# ProPrj_CGM_BH66F2455_HT32F67595_V1_0.net
KiCad netlist of a schematic drawn in EasyEDA Pro
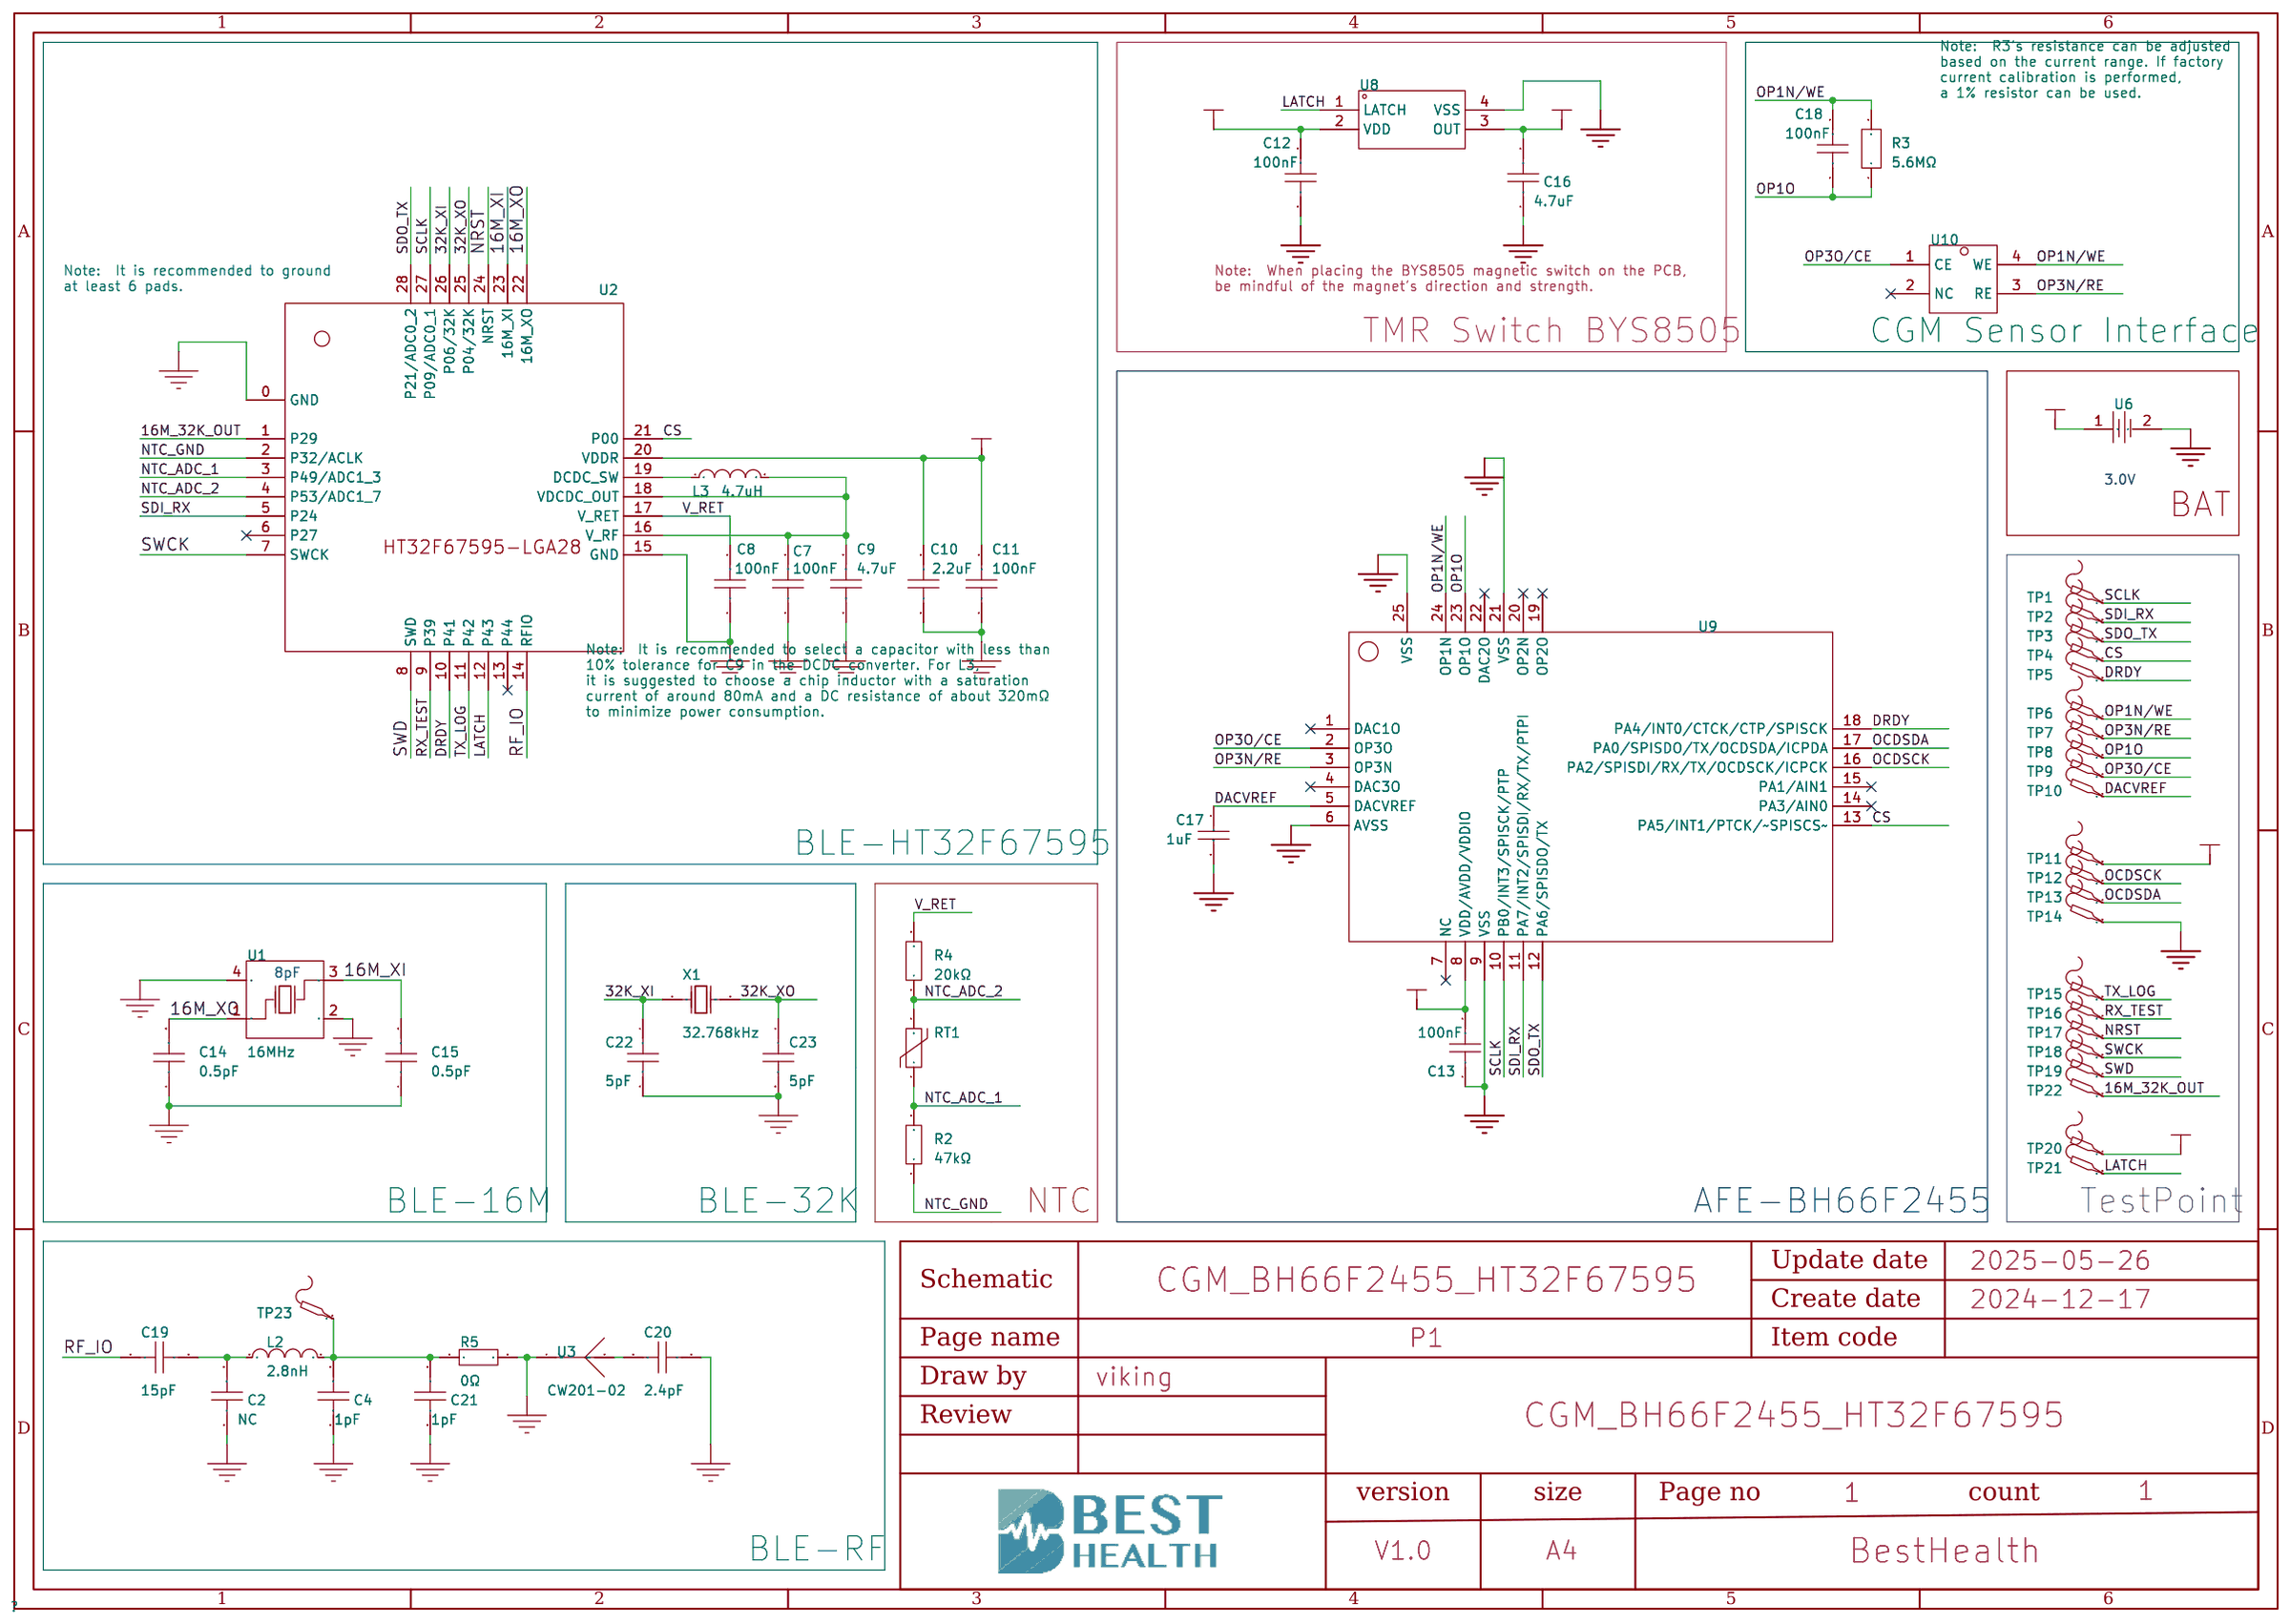
[diagram p0: schematic sheet]

(export (version "E")
  (design (tool "Eeschema 10.0.6"))
  (components
    (comp (ref "C2")
      (value "1.2pF")
      (footprint "easyedapro:C0201")
      (description "容值:1.2pF;额定电压:50V;材质(温度系数):C0G;")
      (fields
        (field (name "Manufacturer Part") "GJM0335C1H1R2WB01D")
        (field (name "Manufacturer") "muRata(村田)")
      )
      (libsource (lib "easyedapro") (part "GJM0335C1H1R2WB01D"))
    )
    (comp (ref "C4")
      (value "1pF")
      (footprint "easyedapro:C0201")
      (description "容值:1pF;精度:-;额定电压:50V;材质(温度系数):C0G;")
      (fields
        (field (name "Manufacturer Part") "GRM0335C1H1R0BA01D")
        (field (name "Manufacturer") "muRata(村田)")
      )
      (libsource (lib "easyedapro") (part "GRM0335C1H1R0BA01D"))
    )
    (comp (ref "C7")
      (value "100nF")
      (footprint "easyedapro:C0201")
      (description "容值:100nF;精度:±10%;额定电压:16V;材质(温度系数):X5R;")
      (fields
        (field (name "Manufacturer Part") "CL03A104KO3NNNC")
        (field (name "Manufacturer") "SAMSUNG(三星)")
      )
      (libsource (lib "easyedapro") (part "CL03A104KO3NNNC"))
    )
    (comp (ref "C8")
      (value "100nF")
      (footprint "easyedapro:C0201")
      (description "容值:100nF;精度:±10%;额定电压:16V;材质(温度系数):X5R;")
      (fields
        (field (name "Manufacturer Part") "CL03A104KO3NNNC")
        (field (name "Manufacturer") "SAMSUNG(三星)")
      )
      (libsource (lib "easyedapro") (part "CL03A104KO3NNNC"))
    )
    (comp (ref "C9")
      (value "4.7uF")
      (footprint "easyedapro:C0402")
      (description "容值:4.7uF;精度:±10%;额定电压:10V;材质(温度系数):X5R;")
      (fields
        (field (name "Manufacturer Part") "CC0402KRX5R6BB475")
        (field (name "Manufacturer") "YAGEO(国巨)")
      )
      (libsource (lib "easyedapro") (part "CC0402KRX5R6BB475"))
    )
    (comp (ref "C10")
      (value "2.2uF")
      (footprint "easyedapro:C0201")
      (description "容值:2.2uF;精度:±20%;额定电压:10V;材质(温度系数):X5R;")
      (fields
        (field (name "Manufacturer Part") "GRM033R61A225ME47D")
        (field (name "Manufacturer") "muRata(村田)")
      )
      (libsource (lib "easyedapro") (part "GRM033R61A225ME47D"))
    )
    (comp (ref "C11")
      (value "100nF")
      (footprint "easyedapro:C0201")
      (description "容值:100nF;精度:±10%;额定电压:16V;材质(温度系数):X5R;")
      (fields
        (field (name "Manufacturer Part") "CL03A104KO3NNNC")
        (field (name "Manufacturer") "SAMSUNG(三星)")
      )
      (libsource (lib "easyedapro") (part "CL03A104KO3NNNC"))
    )
    (comp (ref "C12")
      (value "100nF")
      (footprint "easyedapro:C0201")
      (description "容值:100nF;精度:±10%;额定电压:16V;材质(温度系数):X5R;")
      (fields
        (field (name "Manufacturer Part") "CL03A104KO3NNNC")
        (field (name "Manufacturer") "SAMSUNG(三星)")
      )
      (libsource (lib "easyedapro") (part "CL03A104KO3NNNC"))
    )
    (comp (ref "C13")
      (value "100nF")
      (footprint "easyedapro:C0201")
      (description "容值:100nF;精度:±10%;额定电压:16V;材质(温度系数):X5R;")
      (fields
        (field (name "Manufacturer Part") "CL03A104KO3NNNC")
        (field (name "Manufacturer") "SAMSUNG(三星)")
      )
      (libsource (lib "easyedapro") (part "CL03A104KO3NNNC"))
    )
    (comp (ref "C14")
      (value "0.5pF")
      (footprint "easyedapro:C0201")
      (description "容值:0.5pF;额定电压:50V;温度系数:C0G;")
      (fields
        (field (name "Manufacturer Part") "GRM0335C1HR50BA01D")
        (field (name "Manufacturer") "muRata(村田)")
      )
      (libsource (lib "easyedapro") (part "GRM0335C1HR50BA01D"))
    )
    (comp (ref "C15")
      (value "0.5pF")
      (footprint "easyedapro:C0201")
      (description "容值:0.5pF;额定电压:50V;温度系数:C0G;")
      (fields
        (field (name "Manufacturer Part") "GRM0335C1HR50BA01D")
        (field (name "Manufacturer") "muRata(村田)")
      )
      (libsource (lib "easyedapro") (part "GRM0335C1HR50BA01D"))
    )
    (comp (ref "C16")
      (value "4.7uF")
      (footprint "easyedapro:C0201")
      (description "容值:4.7uF;精度:±20%;额定电压:6.3V;材质(温度系数):X5R;")
      (fields
        (field (name "Manufacturer Part") "GRM035R60J475ME15D")
        (field (name "Manufacturer") "muRata(村田)")
      )
      (libsource (lib "easyedapro") (part "GRM035R60J475ME15D"))
    )
    (comp (ref "C17")
      (value "1uF")
      (footprint "easyedapro:C0201")
      (description "容值:1uF;精度:±20%;额定电压:6.3V;材质(温度系数):X5R;")
      (fields
        (field (name "Manufacturer Part") "CL03A105MQ3CSNH")
        (field (name "Manufacturer") "SAMSUNG(三星)")
      )
      (libsource (lib "easyedapro") (part "CL03A105MQ3CSNH"))
    )
    (comp (ref "C18")
      (value "100nF")
      (footprint "easyedapro:C0201")
      (description "容值:100nF;精度:±10%;额定电压:16V;材质(温度系数):X5R;")
      (fields
        (field (name "Manufacturer Part") "CL03A104KO3NNNC")
        (field (name "Manufacturer") "SAMSUNG(三星)")
      )
      (libsource (lib "easyedapro") (part "CL03A104KO3NNNC"))
    )
    (comp (ref "C19")
      (value "15pF")
      (footprint "easyedapro:C0201")
      (description "容值:15pF;精度:±5%;额定电压:50V;温度系数:C0G;")
      (fields
        (field (name "Manufacturer Part") "GRM0335C1H150JA01D")
        (field (name "Manufacturer") "muRata(村田)")
      )
      (libsource (lib "easyedapro") (part "GRM0335C1H150JA01D"))
    )
    (comp (ref "C20")
      (value "2.4pF")
      (footprint "easyedapro:C0201")
      (description "容值:2.4pF;额定电压:25V;温度系数:C0G;")
      (fields
        (field (name "Manufacturer Part") "GRM0335C1E2R4CA01D")
        (field (name "Manufacturer") "muRata(村田)")
      )
      (libsource (lib "easyedapro") (part "GRM0335C1E2R4CA01D"))
    )
    (comp (ref "C21")
      (value "1pF")
      (footprint "easyedapro:C0201")
      (description "容值:1pF;精度:-;额定电压:50V;材质(温度系数):C0G;")
      (fields
        (field (name "Manufacturer Part") "GRM0335C1H1R0BA01D")
        (field (name "Manufacturer") "muRata(村田)")
      )
      (libsource (lib "easyedapro") (part "GRM0335C1H1R0BA01D"))
    )
    (comp (ref "C22")
      (value "5pF")
      (footprint "easyedapro:C0201")
      (description "容值:5pF;额定电压:25V;材质(温度系数):C0G;")
      (fields
        (field (name "Manufacturer Part") "GJM0335C1E5R0BB01D")
        (field (name "Manufacturer") "muRata(村田)")
      )
      (libsource (lib "easyedapro") (part "GJM0335C1E5R0BB01D"))
    )
    (comp (ref "C23")
      (value "5pF")
      (footprint "easyedapro:C0201")
      (description "容值:5pF;额定电压:25V;材质(温度系数):C0G;")
      (fields
        (field (name "Manufacturer Part") "GJM0335C1E5R0BB01D")
        (field (name "Manufacturer") "muRata(村田)")
      )
      (libsource (lib "easyedapro") (part "GJM0335C1E5R0BB01D"))
    )
    (comp (ref "L2")
      (value "2.8nH")
      (footprint "easyedapro:L0201-RD")
      (description "电感值:2.8nH;精度:-;额定电流:450mA;饱和电流(Isat):-;直流电阻(DCR):250mΩ;")
      (fields (field (name "Manufacturer Part") "LQP03TG2N8B02D") (field (name "Manufacturer") "muRata(村田)"))
      (libsource (lib "easyedapro") (part "LQP03TG2N8B02D"))
    )
    (comp (ref "L3")
      (value "4.7uH")
      (footprint "easyedapro:L0603")
      (description "电感值:4.7uH;精度:±20%;额定电流:-;饱和电流(Isat):80mA;直流电阻(DCR):320mΩ;")
      (fields (field (name "Manufacturer Part") "MLZ1608N4R7LT000") (field (name "Manufacturer") "TDK"))
      (libsource (lib "easyedapro") (part "MLZ1608N4R7LT000"))
    )
    (comp (ref "R2")
      (value "47kΩ")
      (footprint "easyedapro:R0201")
      (description "电阻类型:厚膜电阻;阻值:47kΩ;精度:±1%;功率:50mW;温度系数:±200ppm/°C;最大工作电压:25V;工作温度范围:-55°C~+155°C;")
      (fields (field (name "Manufacturer Part") "RC0201FR-0747KL") (field (name "Manufacturer") "YAGEO(国巨)"))
      (libsource (lib "easyedapro") (part "RC0201FR-0747KL"))
    )
    (comp (ref "R3")
      (value "5.6MΩ")
      (footprint "easyedapro:R0402")
      (description "电阻类型:厚膜电阻;阻值:5.6MΩ;精度:±1%;功率:62.5mW;最大工作电压:50V;温度系数:±100ppm/°C;")
      (fields (field (name "Manufacturer Part") "RC0402FR-075M6L") (field (name "Manufacturer") "YAGEO(国巨)"))
      (libsource (lib "easyedapro") (part "RC0402FR-075M6L"))
    )
    (comp (ref "R4")
      (value "20kΩ")
      (footprint "easyedapro:R0201")
      (description "电阻类型:厚膜电阻;阻值:20kΩ;精度:±1%;功率:50mW;最大工作电压:25V;温度系数:±200ppm/°C;")
      (fields (field (name "Manufacturer Part") "RC0201FR-0720KL") (field (name "Manufacturer") "YAGEO(国巨)"))
      (libsource (lib "easyedapro") (part "RC0201FR-0720KL_C295787"))
    )
    (comp (ref "R5")
      (value "0Ω")
      (footprint "easyedapro:R0201")
      (description "电阻类型:厚膜电阻;阻值:0Ω;精度:±1%;功率:50mW;最大工作电压:25V;温度系数:-;")
      (fields (field (name "Manufacturer Part") "RC0201FR-070RL") (field (name "Manufacturer") "YAGEO(国巨)"))
      (libsource (lib "easyedapro") (part "RC0201FR-070RL"))
    )
    (comp (ref "RT1")
      (value "NTCG064BF473FTBX")
      (footprint "easyedapro:R0201")
      (description "阻值(25°C):47kΩ;电阻精度:±1%;B值精度:±1%;B值(25°C/50°C):4050K;功率:100mW;最大稳态电流(25°C):140uA;")
      (fields (field (name "Manufacturer") "TDK"))
      (libsource (lib "easyedapro") (part "NTCG064BF473FTBX"))
    )
    (comp (ref "TP1")
      (value "TP1")
      (footprint "easyedapro:Test-Point-0.5mm")
      (description "Test Point 测试点")
      (libsource (lib "easyedapro") (part "Test-Point"))
    )
    (comp (ref "TP2")
      (value "TP1")
      (footprint "easyedapro:Test-Point-0.5mm")
      (description "Test Point 测试点")
      (libsource (lib "easyedapro") (part "Test-Point"))
    )
    (comp (ref "TP3")
      (value "TP1")
      (footprint "easyedapro:Test-Point-0.5mm")
      (description "Test Point 测试点")
      (libsource (lib "easyedapro") (part "Test-Point"))
    )
    (comp (ref "TP4")
      (value "TP1")
      (footprint "easyedapro:Test-Point-0.5mm")
      (description "Test Point 测试点")
      (libsource (lib "easyedapro") (part "Test-Point"))
    )
    (comp (ref "TP5")
      (value "TP1")
      (footprint "easyedapro:Test-Point-0.5mm")
      (description "Test Point 测试点")
      (libsource (lib "easyedapro") (part "Test-Point"))
    )
    (comp (ref "TP6")
      (value "TP1")
      (footprint "easyedapro:Test-Point-0.5mm")
      (description "Test Point 测试点")
      (libsource (lib "easyedapro") (part "Test-Point"))
    )
    (comp (ref "TP7")
      (value "TP1")
      (footprint "easyedapro:Test-Point-0.5mm")
      (description "Test Point 测试点")
      (libsource (lib "easyedapro") (part "Test-Point"))
    )
    (comp (ref "TP8")
      (value "TP1")
      (footprint "easyedapro:Test-Point-0.5mm")
      (description "Test Point 测试点")
      (libsource (lib "easyedapro") (part "Test-Point"))
    )
    (comp (ref "TP9")
      (value "TP1")
      (footprint "easyedapro:Test-Point-0.5mm")
      (description "Test Point 测试点")
      (libsource (lib "easyedapro") (part "Test-Point"))
    )
    (comp (ref "TP10")
      (value "TP1")
      (footprint "easyedapro:Test-Point-0.5mm")
      (description "Test Point 测试点")
      (libsource (lib "easyedapro") (part "Test-Point"))
    )
    (comp (ref "TP11")
      (value "TP1")
      (footprint "easyedapro:Test-Point-0.5mm")
      (description "Test Point 测试点")
      (libsource (lib "easyedapro") (part "Test-Point"))
    )
    (comp (ref "TP12")
      (value "TP1")
      (footprint "easyedapro:Test-Point-0.5mm")
      (description "Test Point 测试点")
      (libsource (lib "easyedapro") (part "Test-Point"))
    )
    (comp (ref "TP13")
      (value "TP1")
      (footprint "easyedapro:Test-Point-0.5mm")
      (description "Test Point 测试点")
      (libsource (lib "easyedapro") (part "Test-Point"))
    )
    (comp (ref "TP14")
      (value "TP1")
      (footprint "easyedapro:Test-Point-0.5mm")
      (description "Test Point 测试点")
      (libsource (lib "easyedapro") (part "Test-Point"))
    )
    (comp (ref "TP15")
      (value "~")
      (footprint "easyedapro:Test-Point-0.5mm")
      (description "Test Point 测试点")
      (libsource (lib "easyedapro") (part "Test-Point"))
    )
    (comp (ref "TP16")
      (value "~")
      (footprint "easyedapro:Test-Point-0.5mm")
      (description "Test Point 测试点")
      (libsource (lib "easyedapro") (part "Test-Point"))
    )
    (comp (ref "TP17")
      (value "~")
      (footprint "easyedapro:Test-Point-0.5mm")
      (description "Test Point 测试点")
      (libsource (lib "easyedapro") (part "Test-Point"))
    )
    (comp (ref "TP18")
      (value "~")
      (footprint "easyedapro:Test-Point-0.5mm")
      (description "Test Point 测试点")
      (libsource (lib "easyedapro") (part "Test-Point"))
    )
    (comp (ref "TP19")
      (value "~")
      (footprint "easyedapro:Test-Point-0.5mm")
      (description "Test Point 测试点")
      (libsource (lib "easyedapro") (part "Test-Point"))
    )
    (comp (ref "TP20")
      (value "~")
      (footprint "easyedapro:Test-Point-0.5mm")
      (description "Test Point 测试点")
      (libsource (lib "easyedapro") (part "Test-Point"))
    )
    (comp (ref "TP21")
      (value "~")
      (footprint "easyedapro:Test-Point-0.5mm")
      (description "Test Point 测试点")
      (libsource (lib "easyedapro") (part "Test-Point"))
    )
    (comp (ref "TP22")
      (value "~")
      (footprint "easyedapro:Test-Point-0.5mm")
      (description "Test Point 测试点")
      (libsource (lib "easyedapro") (part "Test-Point"))
    )
    (comp (ref "TP23")
      (value "~")
      (footprint "easyedapro:Test-Point-0.5mm")
      (description "Test Point 测试点")
      (libsource (lib "easyedapro") (part "Test-Point"))
    )
    (comp (ref "U1")
      (value "16MHz")
      (footprint "easyedapro:CRYSTAL-SMD_4P-L2.0-W1.6-BL-A")
      (description "频率:16MHz;负载电容:8pF;频率公差:±10ppm;")
      (fields
        (field (name "Manufacturer Part") "XL7EL89CKI-111YLC-16M")
        (field (name "Manufacturer") "YXC(扬兴晶振)")
      )
      (libsource (lib "easyedapro") (part "XL7EL89CKI-111YLC-16M"))
    )
    (comp (ref "U2")
      (value "HT32F67595_LGA28")
      (footprint "easyedapro:LGA28_L3.0_W3.0mm")
      (libsource (lib "easyedapro") (part "HT32F67595_LGA28"))
    )
    (comp (ref "U3")
      (value "CW201-02")
      (footprint "easyedapro:ANT-SMD_L2.0-W1.2_CW201")
      (fields (field (name "Manufacturer") "LXC(连兴创)"))
      (libsource (lib "easyedapro") (part "CW201-02"))
    )
    (comp (ref "U6")
      (value "CR920")
      (footprint "easyedapro:CR920 Henli Max")
      (description "常州宇峰电池")
      (libsource (lib "easyedapro") (part "CR920 Henli Max"))
    )
    (comp (ref "U8")
      (value "~")
      (footprint "easyedapro:LGA-4_L1.5-W1.5-P0.65-BL")
      (libsource (lib "easyedapro") (part "BYS8505"))
    )
    (comp (ref "U9")
      (value "~")
      (footprint "easyedapro:WQFN-24_L3.0-W3.0-P0.40-TL-EP1.9")
      (description "该单片机是一款 A/D 型具有 8 位高性能精简指令集的 Flash 单片机，内置连续\n血糖监测 AFE 模块，专门为连续血糖监测产品而设计。")
      (fields (field (name "Manufacturer") "HOLTEK"))
      (libsource (lib "easyedapro") (part "BH66F2455"))
    )
    (comp (ref "U10")
      (value "~")
      (footprint "easyedapro:CGM_Sener_V2_TBJ")
      (libsource (lib "easyedapro") (part "CGM_Sensor_V2_TBJ"))
    )
    (comp (ref "X1")
      (value "32.768kHz")
      (footprint "easyedapro:CRYSTAL-SMD_L1.7-W1.1")
      (description "频率:32.768kHz;外接负载电容:12.5pF;")
      (fields (field (name "Manufacturer Part") "X1A0001210005") (field (name "Manufacturer") "EPSON(爱普生)"))
      (libsource (lib "easyedapro") (part "X1A000121000500"))
    )
  )
  (nets
    (net (code "1") (name "/16M_32K_OUT") (class "Default")
      (node (ref "TP22") (pin "1") (pinfunction "1_1") (pintype "input"))
      (node (ref "U2") (pin "1") (pinfunction "P29_1") (pintype "input"))
    )
    (net (code "2") (name "/16M_XI") (class "Default")
      (node (ref "C15") (pin "2") (pinfunction "2_2") (pintype "unspecified"))
      (node (ref "U1") (pin "3") (pinfunction "OSC2_3") (pintype "unspecified"))
      (node (ref "U2") (pin "23") (pinfunction "16M_XI_23") (pintype "input"))
    )
    (net (code "3") (name "/16M_XO") (class "Default")
      (node (ref "C14") (pin "2") (pinfunction "2_2") (pintype "unspecified"))
      (node (ref "U1") (pin "1") (pinfunction "OSC1_1") (pintype "unspecified"))
      (node (ref "U2") (pin "22") (pinfunction "16M_XO_22") (pintype "input"))
    )
    (net (code "4") (name "/32K_XI") (class "Default")
      (node (ref "C22") (pin "1") (pinfunction "1_1") (pintype "unspecified"))
      (node (ref "U2") (pin "26") (pinfunction "P06/32K_26") (pintype "input"))
      (node (ref "X1") (pin "1") (pinfunction "OSC1_1") (pintype "input"))
    )
    (net (code "5") (name "/32K_XO") (class "Default")
      (node (ref "C23") (pin "1") (pinfunction "1_1") (pintype "unspecified"))
      (node (ref "U2") (pin "25") (pinfunction "P04/32K_25") (pintype "input"))
      (node (ref "X1") (pin "2") (pinfunction "OSC2_2") (pintype "input"))
    )
    (net (code "6") (name "/CS") (class "Default")
      (node (ref "TP4") (pin "1") (pinfunction "1_1") (pintype "input"))
      (node (ref "U2") (pin "21") (pinfunction "P00_21") (pintype "input"))
      (node (ref "U9") (pin "13") (pinfunction "PA5/INT1/PTCK/~SPISCS~_13") (pintype "input"))
    )
    (net (code "7") (name "/DACVREF") (class "Default")
      (node (ref "C17") (pin "1") (pinfunction "1_1") (pintype "input"))
      (node (ref "TP10") (pin "1") (pinfunction "1_1") (pintype "input"))
      (node (ref "U9") (pin "5") (pinfunction "DACVREF_5") (pintype "input"))
    )
    (net (code "8") (name "/DRDY") (class "Default")
      (node (ref "TP5") (pin "1") (pinfunction "1_1") (pintype "input"))
      (node (ref "U2") (pin "10") (pinfunction "P41_10") (pintype "input"))
      (node (ref "U9") (pin "18") (pinfunction "PA4/INT0/CTCK/CTP/SPISCK_18") (pintype "input"))
    )
    (net (code "9") (name "/LATCH") (class "Default")
      (node (ref "TP21") (pin "1") (pinfunction "1_1") (pintype "input"))
      (node (ref "U2") (pin "12") (pinfunction "P43_12") (pintype "input"))
      (node (ref "U8") (pin "1") (pinfunction "LATCH_1") (pintype "input"))
    )
    (net (code "10") (name "/NRST") (class "Default")
      (node (ref "TP17") (pin "1") (pinfunction "1_1") (pintype "input"))
      (node (ref "U2") (pin "24") (pinfunction "NRST_24") (pintype "input"))
    )
    (net (code "11") (name "/NTC_ADC_1") (class "Default")
      (node (ref "R2") (pin "2") (pinfunction "2_2") (pintype "input"))
      (node (ref "RT1") (pin "1") (pinfunction "1_1") (pintype "input"))
      (node (ref "U2") (pin "3") (pinfunction "P49/ADC1_3_3") (pintype "input"))
    )
    (net (code "12") (name "/NTC_ADC_2") (class "Default")
      (node (ref "R4") (pin "1") (pinfunction "1_1") (pintype "unspecified"))
      (node (ref "RT1") (pin "2") (pinfunction "2_2") (pintype "input"))
      (node (ref "U2") (pin "4") (pinfunction "P53/ADC1_7_4") (pintype "input"))
    )
    (net (code "13") (name "/NTC_GND") (class "Default")
      (node (ref "R2") (pin "1") (pinfunction "1_1") (pintype "input"))
      (node (ref "U2") (pin "2") (pinfunction "P32/ACLK_2") (pintype "input"))
    )
    (net (code "14") (name "/OCDSCK") (class "Default")
      (node (ref "TP12") (pin "1") (pinfunction "1_1") (pintype "input"))
      (node (ref "U9") (pin "16") (pinfunction "PA2/SPISDI/RX/TX/OCDSCK/ICPCK_16") (pintype "input"))
    )
    (net (code "15") (name "/OCDSDA") (class "Default")
      (node (ref "TP13") (pin "1") (pinfunction "1_1") (pintype "input"))
      (node (ref "U9") (pin "17") (pinfunction "PA0/SPISDO/TX/OCDSDA/ICPDA_17") (pintype "input"))
    )
    (net (code "16") (name "/OP1N{slash}WE") (class "Default")
      (node (ref "C18") (pin "2") (pinfunction "2_2") (pintype "input"))
      (node (ref "R3") (pin "2") (pinfunction "2_2") (pintype "unspecified"))
      (node (ref "TP6") (pin "1") (pinfunction "1_1") (pintype "input"))
      (node (ref "U10") (pin "4") (pinfunction "WE_4") (pintype "input"))
      (node (ref "U9") (pin "24") (pinfunction "OP1N_24") (pintype "input"))
    )
    (net (code "17") (name "/OP1O") (class "Default")
      (node (ref "C18") (pin "1") (pinfunction "1_1") (pintype "input"))
      (node (ref "R3") (pin "1") (pinfunction "1_1") (pintype "unspecified"))
      (node (ref "TP8") (pin "1") (pinfunction "1_1") (pintype "input"))
      (node (ref "U9") (pin "23") (pinfunction "OP1O_23") (pintype "input"))
    )
    (net (code "18") (name "/OP3N{slash}RE") (class "Default")
      (node (ref "TP7") (pin "1") (pinfunction "1_1") (pintype "input"))
      (node (ref "U10") (pin "3") (pinfunction "RE_3") (pintype "input"))
      (node (ref "U9") (pin "3") (pinfunction "OP3N_3") (pintype "input"))
    )
    (net (code "19") (name "/OP3O{slash}CE") (class "Default")
      (node (ref "TP9") (pin "1") (pinfunction "1_1") (pintype "input"))
      (node (ref "U10") (pin "1") (pinfunction "CE_1") (pintype "input"))
      (node (ref "U9") (pin "2") (pinfunction "OP3O_2") (pintype "input"))
    )
    (net (code "20") (name "/RF_IO") (class "Default")
      (node (ref "C19") (pin "1") (pinfunction "1_1") (pintype "unspecified"))
      (node (ref "U2") (pin "14") (pinfunction "RFIO_14") (pintype "input"))
    )
    (net (code "21") (name "/RX_TEST") (class "Default")
      (node (ref "TP16") (pin "1") (pinfunction "1_1") (pintype "input"))
      (node (ref "U2") (pin "9") (pinfunction "P39_9") (pintype "input"))
    )
    (net (code "22") (name "/SCLK") (class "Default")
      (node (ref "TP1") (pin "1") (pinfunction "1_1") (pintype "input"))
      (node (ref "U2") (pin "27") (pinfunction "P09/ADC0_1_27") (pintype "input"))
      (node (ref "U9") (pin "10") (pinfunction "PB0/INT3/SPISCK/PTP_10") (pintype "input"))
    )
    (net (code "23") (name "/SDI_RX") (class "Default")
      (node (ref "TP2") (pin "1") (pinfunction "1_1") (pintype "input"))
      (node (ref "U2") (pin "5") (pinfunction "P24_5") (pintype "input"))
      (node (ref "U9") (pin "11") (pinfunction "PA7/INT2/SPISDI/RX/TX/PTPI_11") (pintype "input"))
    )
    (net (code "24") (name "/SDO_TX") (class "Default")
      (node (ref "TP3") (pin "1") (pinfunction "1_1") (pintype "input"))
      (node (ref "U2") (pin "28") (pinfunction "P21/ADC0_2_28") (pintype "input"))
      (node (ref "U9") (pin "12") (pinfunction "PA6/SPISDO/TX_12") (pintype "input"))
    )
    (net (code "25") (name "/SWCK") (class "Default")
      (node (ref "TP18") (pin "1") (pinfunction "1_1") (pintype "input"))
      (node (ref "U2") (pin "7") (pinfunction "SWCK_7") (pintype "input"))
    )
    (net (code "26") (name "/SWD") (class "Default")
      (node (ref "TP19") (pin "1") (pinfunction "1_1") (pintype "input"))
      (node (ref "U2") (pin "8") (pinfunction "SWD_8") (pintype "input"))
    )
    (net (code "27") (name "/TX_LOG") (class "Default")
      (node (ref "TP15") (pin "1") (pinfunction "1_1") (pintype "input"))
      (node (ref "U2") (pin "11") (pinfunction "P42_11") (pintype "input"))
    )
    (net (code "28") (name "/V_RET") (class "Default")
      (node (ref "C8") (pin "2") (pinfunction "2_2") (pintype "input"))
      (node (ref "R4") (pin "2") (pinfunction "2_2") (pintype "unspecified"))
      (node (ref "U2") (pin "17") (pinfunction "V_RET_17") (pintype "input"))
    )
    (net (code "29") (name "GND") (class "Default")
      (node (ref "C10") (pin "1") (pinfunction "1_1") (pintype "unspecified"))
      (node (ref "C11") (pin "1") (pinfunction "1_1") (pintype "input"))
      (node (ref "C12") (pin "1") (pinfunction "1_1") (pintype "input"))
      (node (ref "C13") (pin "1") (pinfunction "1_1") (pintype "input"))
      (node (ref "C14") (pin "1") (pinfunction "1_1") (pintype "unspecified"))
      (node (ref "C15") (pin "1") (pinfunction "1_1") (pintype "unspecified"))
      (node (ref "C16") (pin "1") (pinfunction "1_1") (pintype "unspecified"))
      (node (ref "C17") (pin "2") (pinfunction "2_2") (pintype "input"))
      (node (ref "C2") (pin "1") (pinfunction "1_1") (pintype "unspecified"))
      (node (ref "C20") (pin "1") (pinfunction "1_1") (pintype "unspecified"))
      (node (ref "C21") (pin "1") (pinfunction "1_1") (pintype "unspecified"))
      (node (ref "C22") (pin "2") (pinfunction "2_2") (pintype "unspecified"))
      (node (ref "C23") (pin "2") (pinfunction "2_2") (pintype "unspecified"))
      (node (ref "C4") (pin "1") (pinfunction "1_1") (pintype "unspecified"))
      (node (ref "C7") (pin "1") (pinfunction "1_1") (pintype "input"))
      (node (ref "C8") (pin "1") (pinfunction "1_1") (pintype "input"))
      (node (ref "C9") (pin "1") (pinfunction "1_1") (pintype "unspecified"))
      (node (ref "R5") (pin "2") (pinfunction "2_2") (pintype "unspecified"))
      (node (ref "TP14") (pin "1") (pinfunction "1_1") (pintype "input"))
      (node (ref "U1") (pin "2") (pinfunction "GND_2") (pintype "unspecified"))
      (node (ref "U1") (pin "4") (pinfunction "GND_4") (pintype "unspecified"))
      (node (ref "U2") (pin "0") (pinfunction "GND_0") (pintype "input"))
      (node (ref "U2") (pin "15") (pinfunction "GND_15") (pintype "input"))
      (node (ref "U3") (pin "1") (pinfunction "Signal_Input_1") (pintype "unspecified"))
      (node (ref "U6") (pin "2") (pinfunction "2_2") (pintype "input"))
      (node (ref "U8") (pin "4") (pinfunction "VSS_4") (pintype "input"))
      (node (ref "U9") (pin "21") (pinfunction "VSS_21") (pintype "input"))
      (node (ref "U9") (pin "25") (pinfunction "VSS_25") (pintype "input"))
      (node (ref "U9") (pin "6") (pinfunction "AVSS_6") (pintype "input"))
      (node (ref "U9") (pin "9") (pinfunction "VSS_9") (pintype "input"))
    )
    (net (code "30") (name "Net-(C19-Pad2)") (class "Default")
      (node (ref "C19") (pin "2") (pinfunction "2_2") (pintype "unspecified"))
      (node (ref "C2") (pin "2") (pinfunction "2_2") (pintype "unspecified"))
      (node (ref "L2") (pin "1") (pinfunction "1_1") (pintype "unspecified"))
    )
    (net (code "31") (name "Net-(C21-Pad2)") (class "Default")
      (node (ref "C21") (pin "2") (pinfunction "2_2") (pintype "unspecified"))
      (node (ref "C4") (pin "2") (pinfunction "2_2") (pintype "unspecified"))
      (node (ref "L2") (pin "2") (pinfunction "2_2") (pintype "unspecified"))
      (node (ref "R5") (pin "1") (pinfunction "1_1") (pintype "unspecified"))
      (node (ref "TP23") (pin "1") (pinfunction "1_1") (pintype "input"))
    )
    (net (code "32") (name "Net-(U2-DCDC_SW)") (class "Default")
      (node (ref "L3") (pin "1") (pinfunction "1_1") (pintype "unspecified"))
      (node (ref "U2") (pin "19") (pinfunction "DCDC_SW_19") (pintype "input"))
    )
    (net (code "33") (name "Net-(U2-VDCDC_OUT)") (class "Default")
      (node (ref "C7") (pin "2") (pinfunction "2_2") (pintype "input"))
      (node (ref "C9") (pin "2") (pinfunction "2_2") (pintype "unspecified"))
      (node (ref "L3") (pin "2") (pinfunction "2_2") (pintype "unspecified"))
      (node (ref "U2") (pin "16") (pinfunction "V_RF_16") (pintype "input"))
      (node (ref "U2") (pin "18") (pinfunction "VDCDC_OUT_18") (pintype "input"))
    )
    (net (code "34") (name "Net-(U3-Tuning{slash}Signal_Output)") (class "Default")
      (node (ref "C20") (pin "2") (pinfunction "2_2") (pintype "unspecified"))
      (node (ref "U3") (pin "2") (pinfunction "Tuning/Signal_Output_2") (pintype "unspecified"))
    )
    (net (code "35") (name "VBAT") (class "Default")
      (node (ref "C12") (pin "2") (pinfunction "2_2") (pintype "input"))
      (node (ref "TP20") (pin "1") (pinfunction "1_1") (pintype "input"))
      (node (ref "U6") (pin "1") (pinfunction "1_1") (pintype "input"))
      (node (ref "U8") (pin "2") (pinfunction "VDD_2") (pintype "input"))
    )
    (net (code "36") (name "VDD") (class "Default")
      (node (ref "C10") (pin "2") (pinfunction "2_2") (pintype "unspecified"))
      (node (ref "C11") (pin "2") (pinfunction "2_2") (pintype "input"))
      (node (ref "C13") (pin "2") (pinfunction "2_2") (pintype "input"))
      (node (ref "C16") (pin "2") (pinfunction "2_2") (pintype "unspecified"))
      (node (ref "TP11") (pin "1") (pinfunction "1_1") (pintype "input"))
      (node (ref "U2") (pin "20") (pinfunction "VDDR_20") (pintype "input"))
      (node (ref "U8") (pin "3") (pinfunction "OUT_3") (pintype "input"))
      (node (ref "U9") (pin "8") (pinfunction "VDD/AVDD/VDDIO_8") (pintype "input"))
    )
    (net (code "37") (name "unconnected-(U2-P27-Pad6)") (class "Default")
      (node (ref "U2") (pin "6") (pinfunction "P27_6") (pintype "input+no_connect"))
    )
    (net (code "38") (name "unconnected-(U2-P44-Pad13)") (class "Default")
      (node (ref "U2") (pin "13") (pinfunction "P44_13") (pintype "input+no_connect"))
    )
    (net (code "39") (name "unconnected-(U9-DAC1O-Pad1)") (class "Default")
      (node (ref "U9") (pin "1") (pinfunction "DAC1O_1") (pintype "input+no_connect"))
    )
    (net (code "40") (name "unconnected-(U9-DAC2O-Pad22)") (class "Default")
      (node (ref "U9") (pin "22") (pinfunction "DAC2O_22") (pintype "input+no_connect"))
    )
    (net (code "41") (name "unconnected-(U9-DAC3O-Pad4)") (class "Default")
      (node (ref "U9") (pin "4") (pinfunction "DAC3O_4") (pintype "input+no_connect"))
    )
    (net (code "42") (name "unconnected-(U9-NC-Pad7)") (class "Default")
      (node (ref "U9") (pin "7") (pinfunction "NC_7") (pintype "input+no_connect"))
    )
    (net (code "43") (name "unconnected-(U9-OP2N-Pad20)") (class "Default")
      (node (ref "U9") (pin "20") (pinfunction "OP2N_20") (pintype "input+no_connect"))
    )
    (net (code "44") (name "unconnected-(U9-OP2O-Pad19)") (class "Default")
      (node (ref "U9") (pin "19") (pinfunction "OP2O_19") (pintype "input+no_connect"))
    )
    (net (code "45") (name "unconnected-(U9-PA1{slash}AIN1-Pad15)") (class "Default")
      (node (ref "U9") (pin "15") (pinfunction "PA1/AIN1_15") (pintype "input+no_connect"))
    )
    (net (code "46") (name "unconnected-(U9-PA3{slash}AIN0-Pad14)") (class "Default")
      (node (ref "U9") (pin "14") (pinfunction "PA3/AIN0_14") (pintype "input+no_connect"))
    )
    (net (code "47") (name "unconnected-(U10-NC-Pad2)") (class "Default")
      (node (ref "U10") (pin "2") (pinfunction "NC_2") (pintype "input+no_connect"))
    )
  )
)
